# drums_01_1.net
KiCad netlist of a schematic drawn in EAGLE
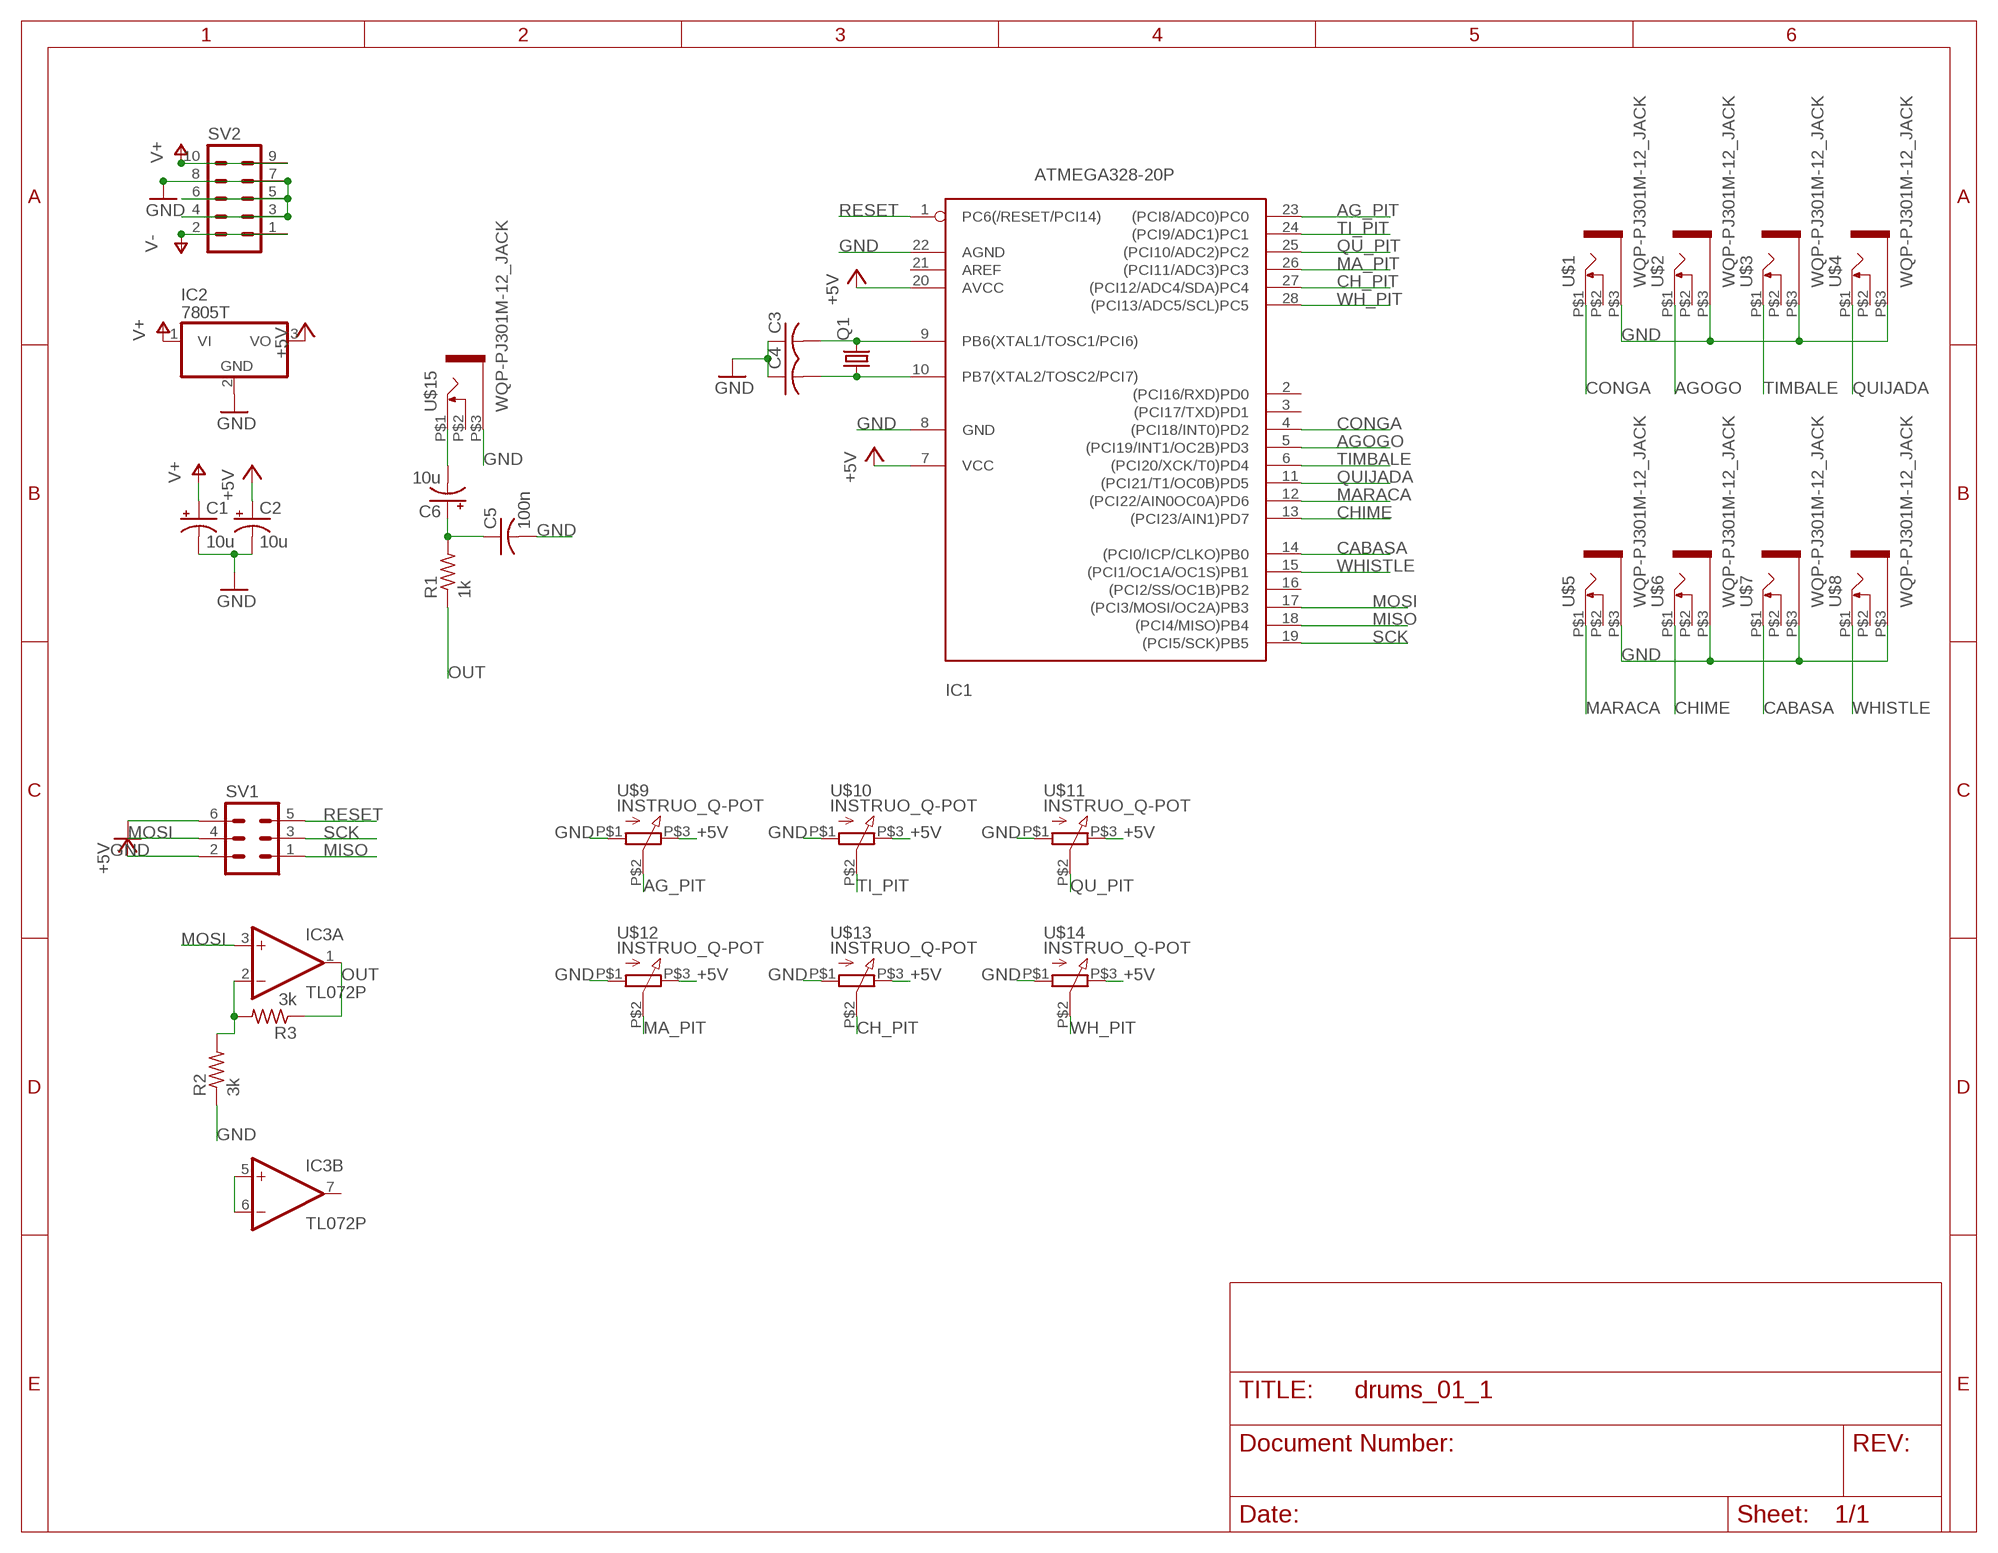
[diagram p0: schematic, sheet 1]

(export (version "E")
  (design (tool "Eeschema 10.0.6"))
  (components
    (comp (ref "C1")
      (value "10u")
      (footprint "eagle-import:E2,5-6")
      (libsource (lib "eagle-import") (part "CPOL-USE2.5-6"))
    )
    (comp (ref "C2")
      (value "10u")
      (footprint "eagle-import:E2,5-6")
      (libsource (lib "eagle-import") (part "CPOL-USE2.5-6"))
    )
    (comp (ref "C3")
      (value "C-US025-024X044")
      (footprint "eagle-import:C025-024X044")
      (libsource (lib "eagle-import") (part "C-US025-024X044"))
    )
    (comp (ref "C4")
      (value "C-US025-024X044")
      (footprint "eagle-import:C025-024X044")
      (libsource (lib "eagle-import") (part "C-US025-024X044"))
    )
    (comp (ref "C5")
      (value "100n")
      (footprint "eagle-import:C025-024X044")
      (libsource (lib "eagle-import") (part "C-US025-024X044"))
    )
    (comp (ref "C6")
      (value "10u")
      (footprint "eagle-import:E2,5-6")
      (libsource (lib "eagle-import") (part "CPOL-USE2.5-6"))
    )
    (comp (ref "IC1")
      (value "ATMEGA328-20P")
      (footprint "eagle-import:DIL28-3")
      (libsource (lib "eagle-import") (part "ATMEGA328P-20"))
    )
    (comp (ref "IC2")
      (value "7805T")
      (footprint "eagle-import:TO220H")
      (libsource (lib "eagle-import") (part "78T05"))
    )
    (comp (ref "IC3")
      (value "TL072P")
      (footprint "eagle-import:DIL08")
      (libsource (lib "eagle-import") (part "TL072P"))
    )
    (comp (ref "Q1")
      (value "CRYSTALHC49U-V")
      (footprint "eagle-import:HC49U-V")
      (libsource (lib "eagle-import") (part "CRYSTALHC49U-V"))
    )
    (comp (ref "R1")
      (value "1k")
      (footprint "eagle-import:0207_12")
      (libsource (lib "eagle-import") (part "R-US_0207/12"))
    )
    (comp (ref "R2")
      (value "3k")
      (footprint "eagle-import:0207_12")
      (libsource (lib "eagle-import") (part "R-US_0207/12"))
    )
    (comp (ref "R3")
      (value "3k")
      (footprint "eagle-import:0207_12")
      (libsource (lib "eagle-import") (part "R-US_0207/12"))
    )
    (comp (ref "SV1")
      (value "MA03-2")
      (footprint "eagle-import:MA03-2")
      (libsource (lib "eagle-import") (part "MA03-2"))
    )
    (comp (ref "SV2")
      (value "MA05-2")
      (footprint "eagle-import:MA05-2")
      (libsource (lib "eagle-import") (part "MA05-2"))
    )
    (comp (ref "U$1")
      (value "WQP-PJ301M-12_JACK")
      (footprint "eagle-import:WQP-PJ301M-12_JACK")
      (libsource (lib "eagle-import") (part "WQP-PJ301M-12_JACK"))
    )
    (comp (ref "U$2")
      (value "WQP-PJ301M-12_JACK")
      (footprint "eagle-import:WQP-PJ301M-12_JACK")
      (libsource (lib "eagle-import") (part "WQP-PJ301M-12_JACK"))
    )
    (comp (ref "U$3")
      (value "WQP-PJ301M-12_JACK")
      (footprint "eagle-import:WQP-PJ301M-12_JACK")
      (libsource (lib "eagle-import") (part "WQP-PJ301M-12_JACK"))
    )
    (comp (ref "U$4")
      (value "WQP-PJ301M-12_JACK")
      (footprint "eagle-import:WQP-PJ301M-12_JACK")
      (libsource (lib "eagle-import") (part "WQP-PJ301M-12_JACK"))
    )
    (comp (ref "U$5")
      (value "WQP-PJ301M-12_JACK")
      (footprint "eagle-import:WQP-PJ301M-12_JACK")
      (libsource (lib "eagle-import") (part "WQP-PJ301M-12_JACK"))
    )
    (comp (ref "U$6")
      (value "WQP-PJ301M-12_JACK")
      (footprint "eagle-import:WQP-PJ301M-12_JACK")
      (libsource (lib "eagle-import") (part "WQP-PJ301M-12_JACK"))
    )
    (comp (ref "U$7")
      (value "WQP-PJ301M-12_JACK")
      (footprint "eagle-import:WQP-PJ301M-12_JACK")
      (libsource (lib "eagle-import") (part "WQP-PJ301M-12_JACK"))
    )
    (comp (ref "U$8")
      (value "WQP-PJ301M-12_JACK")
      (footprint "eagle-import:WQP-PJ301M-12_JACK")
      (libsource (lib "eagle-import") (part "WQP-PJ301M-12_JACK"))
    )
    (comp (ref "U$9")
      (value "INSTRUO_Q-POT")
      (footprint "eagle-import:INSTRUO_Q-POT")
      (libsource (lib "eagle-import") (part "INSTRUO_Q-POT"))
    )
    (comp (ref "U$10")
      (value "INSTRUO_Q-POT")
      (footprint "eagle-import:INSTRUO_Q-POT")
      (libsource (lib "eagle-import") (part "INSTRUO_Q-POT"))
    )
    (comp (ref "U$11")
      (value "INSTRUO_Q-POT")
      (footprint "eagle-import:INSTRUO_Q-POT")
      (libsource (lib "eagle-import") (part "INSTRUO_Q-POT"))
    )
    (comp (ref "U$12")
      (value "INSTRUO_Q-POT")
      (footprint "eagle-import:INSTRUO_Q-POT")
      (libsource (lib "eagle-import") (part "INSTRUO_Q-POT"))
    )
    (comp (ref "U$13")
      (value "INSTRUO_Q-POT")
      (footprint "eagle-import:INSTRUO_Q-POT")
      (libsource (lib "eagle-import") (part "INSTRUO_Q-POT"))
    )
    (comp (ref "U$14")
      (value "INSTRUO_Q-POT")
      (footprint "eagle-import:INSTRUO_Q-POT")
      (libsource (lib "eagle-import") (part "INSTRUO_Q-POT"))
    )
    (comp (ref "U$15")
      (value "WQP-PJ301M-12_JACK")
      (footprint "eagle-import:WQP-PJ301M-12_JACK")
      (libsource (lib "eagle-import") (part "WQP-PJ301M-12_JACK"))
    )
  )
  (nets
    (net (code "1") (name "+5V") (class "Default")
      (node (ref "C2") (pin "+") (pinfunction "+_+") (pintype "passive"))
      (node (ref "IC1") (pin "20") (pinfunction "AVCC_20") (pintype "bidirectional"))
      (node (ref "IC1") (pin "7") (pinfunction "VCC_7") (pintype "bidirectional"))
      (node (ref "IC2") (pin "3") (pinfunction "VO_3") (pintype "passive"))
      (node (ref "SV1") (pin "2") (pinfunction "2_2") (pintype "passive"))
      (node (ref "U$10") (pin "P$3") (pinfunction "3_P$3") (pintype "passive"))
      (node (ref "U$11") (pin "P$3") (pinfunction "3_P$3") (pintype "passive"))
      (node (ref "U$12") (pin "P$3") (pinfunction "3_P$3") (pintype "passive"))
      (node (ref "U$13") (pin "P$3") (pinfunction "3_P$3") (pintype "passive"))
      (node (ref "U$14") (pin "P$3") (pinfunction "3_P$3") (pintype "passive"))
      (node (ref "U$9") (pin "P$3") (pinfunction "3_P$3") (pintype "passive"))
    )
    (net (code "2") (name "/AGOGO") (class "Default")
      (node (ref "IC1") (pin "5") (pinfunction "(PCI19/INT1/OC2B)PD3_5") (pintype "bidirectional"))
      (node (ref "U$2") (pin "P$1") (pinfunction "2_P$1") (pintype "passive"))
    )
    (net (code "3") (name "/AG_PIT") (class "Default")
      (node (ref "IC1") (pin "23") (pinfunction "(PCI8/ADC0)PC0_23") (pintype "bidirectional"))
      (node (ref "U$9") (pin "P$2") (pinfunction "2_P$2") (pintype "passive"))
    )
    (net (code "4") (name "/CABASA") (class "Default")
      (node (ref "IC1") (pin "14") (pinfunction "(PCI0/ICP/CLKO)PB0_14") (pintype "bidirectional"))
      (node (ref "U$7") (pin "P$1") (pinfunction "2_P$1") (pintype "passive"))
    )
    (net (code "5") (name "/CHIME") (class "Default")
      (node (ref "IC1") (pin "13") (pinfunction "(PCI23/AIN1)PD7_13") (pintype "bidirectional"))
      (node (ref "U$6") (pin "P$1") (pinfunction "2_P$1") (pintype "passive"))
    )
    (net (code "6") (name "/CH_PIT") (class "Default")
      (node (ref "IC1") (pin "27") (pinfunction "(PCI12/ADC4/SDA)PC4_27") (pintype "bidirectional"))
      (node (ref "U$13") (pin "P$2") (pinfunction "2_P$2") (pintype "passive"))
    )
    (net (code "7") (name "/CONGA") (class "Default")
      (node (ref "IC1") (pin "4") (pinfunction "(PCI18/INT0)PD2_4") (pintype "bidirectional"))
      (node (ref "U$1") (pin "P$1") (pinfunction "2_P$1") (pintype "passive"))
    )
    (net (code "8") (name "/MARACA") (class "Default")
      (node (ref "IC1") (pin "12") (pinfunction "(PCI22/AIN0OC0A)PD6_12") (pintype "bidirectional"))
      (node (ref "U$5") (pin "P$1") (pinfunction "2_P$1") (pintype "passive"))
    )
    (net (code "9") (name "/MA_PIT") (class "Default")
      (node (ref "IC1") (pin "26") (pinfunction "(PCI11/ADC3)PC3_26") (pintype "bidirectional"))
      (node (ref "U$12") (pin "P$2") (pinfunction "2_P$2") (pintype "passive"))
    )
    (net (code "10") (name "/MISO") (class "Default")
      (node (ref "IC1") (pin "18") (pinfunction "(PCI4/MISO)PB4_18") (pintype "bidirectional"))
      (node (ref "SV1") (pin "1") (pinfunction "1_1") (pintype "passive"))
    )
    (net (code "11") (name "/MOSI") (class "Default")
      (node (ref "IC1") (pin "17") (pinfunction "(PCI3/MOSI/OC2A)PB3_17") (pintype "bidirectional"))
      (node (ref "IC3") (pin "3") (pinfunction "+IN_3") (pintype "input"))
      (node (ref "SV1") (pin "4") (pinfunction "4_4") (pintype "passive"))
    )
    (net (code "12") (name "/OUT") (class "Default")
      (node (ref "IC3") (pin "1") (pinfunction "OUT_1") (pintype "output"))
      (node (ref "R1") (pin "1") (pinfunction "1_1") (pintype "passive"))
      (node (ref "R3") (pin "1") (pinfunction "1_1") (pintype "passive"))
    )
    (net (code "13") (name "/QUIJADA") (class "Default")
      (node (ref "IC1") (pin "11") (pinfunction "(PCI21/T1/OC0B)PD5_11") (pintype "bidirectional"))
      (node (ref "U$4") (pin "P$1") (pinfunction "2_P$1") (pintype "passive"))
    )
    (net (code "14") (name "/QU_PIT") (class "Default")
      (node (ref "IC1") (pin "25") (pinfunction "(PCI10/ADC2)PC2_25") (pintype "bidirectional"))
      (node (ref "U$11") (pin "P$2") (pinfunction "2_P$2") (pintype "passive"))
    )
    (net (code "15") (name "/RESET") (class "Default")
      (node (ref "IC1") (pin "1") (pinfunction "PC6(/RESET/PCI14)_1") (pintype "bidirectional"))
      (node (ref "SV1") (pin "5") (pinfunction "5_5") (pintype "passive"))
    )
    (net (code "16") (name "/SCK") (class "Default")
      (node (ref "IC1") (pin "19") (pinfunction "(PCI5/SCK)PB5_19") (pintype "bidirectional"))
      (node (ref "SV1") (pin "3") (pinfunction "3_3") (pintype "passive"))
    )
    (net (code "17") (name "/TIMBALE") (class "Default")
      (node (ref "IC1") (pin "6") (pinfunction "(PCI20/XCK/T0)PD4_6") (pintype "bidirectional"))
      (node (ref "U$3") (pin "P$1") (pinfunction "2_P$1") (pintype "passive"))
    )
    (net (code "18") (name "/TI_PIT") (class "Default")
      (node (ref "IC1") (pin "24") (pinfunction "(PCI9/ADC1)PC1_24") (pintype "bidirectional"))
      (node (ref "U$10") (pin "P$2") (pinfunction "2_P$2") (pintype "passive"))
    )
    (net (code "19") (name "/WHISTLE") (class "Default")
      (node (ref "IC1") (pin "15") (pinfunction "(PCI1/OC1A/OC1S)PB1_15") (pintype "bidirectional"))
      (node (ref "U$8") (pin "P$1") (pinfunction "2_P$1") (pintype "passive"))
    )
    (net (code "20") (name "/WH_PIT") (class "Default")
      (node (ref "IC1") (pin "28") (pinfunction "(PCI13/ADC5/SCL)PC5_28") (pintype "bidirectional"))
      (node (ref "U$14") (pin "P$2") (pinfunction "2_P$2") (pintype "passive"))
    )
    (net (code "21") (name "GND") (class "Default")
      (node (ref "C1") (pin "-") (pinfunction "-_-") (pintype "passive"))
      (node (ref "C2") (pin "-") (pinfunction "-_-") (pintype "passive"))
      (node (ref "C3") (pin "1") (pinfunction "1_1") (pintype "passive"))
      (node (ref "C4") (pin "1") (pinfunction "1_1") (pintype "passive"))
      (node (ref "C5") (pin "2") (pinfunction "2_2") (pintype "passive"))
      (node (ref "IC1") (pin "22") (pinfunction "AGND_22") (pintype "bidirectional"))
      (node (ref "IC1") (pin "8") (pinfunction "GND_8") (pintype "bidirectional"))
      (node (ref "IC2") (pin "2") (pinfunction "GND_2") (pintype "passive"))
      (node (ref "R2") (pin "1") (pinfunction "1_1") (pintype "passive"))
      (node (ref "SV1") (pin "6") (pinfunction "6_6") (pintype "passive"))
      (node (ref "SV2") (pin "3") (pinfunction "3_3") (pintype "passive"))
      (node (ref "SV2") (pin "4") (pinfunction "4_4") (pintype "passive"))
      (node (ref "SV2") (pin "5") (pinfunction "5_5") (pintype "passive"))
      (node (ref "SV2") (pin "6") (pinfunction "6_6") (pintype "passive"))
      (node (ref "SV2") (pin "7") (pinfunction "7_7") (pintype "passive"))
      (node (ref "SV2") (pin "8") (pinfunction "8_8") (pintype "passive"))
      (node (ref "U$1") (pin "P$3") (pinfunction "1_P$3") (pintype "passive"))
      (node (ref "U$10") (pin "P$1") (pinfunction "1_P$1") (pintype "passive"))
      (node (ref "U$11") (pin "P$1") (pinfunction "1_P$1") (pintype "passive"))
      (node (ref "U$12") (pin "P$1") (pinfunction "1_P$1") (pintype "passive"))
      (node (ref "U$13") (pin "P$1") (pinfunction "1_P$1") (pintype "passive"))
      (node (ref "U$14") (pin "P$1") (pinfunction "1_P$1") (pintype "passive"))
      (node (ref "U$15") (pin "P$3") (pinfunction "1_P$3") (pintype "passive"))
      (node (ref "U$2") (pin "P$3") (pinfunction "1_P$3") (pintype "passive"))
      (node (ref "U$3") (pin "P$3") (pinfunction "1_P$3") (pintype "passive"))
      (node (ref "U$4") (pin "P$3") (pinfunction "1_P$3") (pintype "passive"))
      (node (ref "U$5") (pin "P$3") (pinfunction "1_P$3") (pintype "passive"))
      (node (ref "U$6") (pin "P$3") (pinfunction "1_P$3") (pintype "passive"))
      (node (ref "U$7") (pin "P$3") (pinfunction "1_P$3") (pintype "passive"))
      (node (ref "U$8") (pin "P$3") (pinfunction "1_P$3") (pintype "passive"))
      (node (ref "U$9") (pin "P$1") (pinfunction "1_P$1") (pintype "passive"))
    )
    (net (code "22") (name "Net-(C5-Pad1)") (class "Default")
      (node (ref "C5") (pin "1") (pinfunction "1_1") (pintype "passive"))
      (node (ref "C6") (pin "+") (pinfunction "+_+") (pintype "passive"))
      (node (ref "R1") (pin "2") (pinfunction "2_2") (pintype "passive"))
    )
    (net (code "23") (name "Net-(IC1-PB6(XTAL1{slash}TOSC1{slash}PCI6))") (class "Default")
      (node (ref "C3") (pin "2") (pinfunction "2_2") (pintype "passive"))
      (node (ref "IC1") (pin "9") (pinfunction "PB6(XTAL1/TOSC1/PCI6)_9") (pintype "bidirectional"))
      (node (ref "Q1") (pin "2") (pinfunction "2_2") (pintype "passive"))
    )
    (net (code "24") (name "Net-(IC1-PB7(XTAL2{slash}TOSC2{slash}PCI7))") (class "Default")
      (node (ref "C4") (pin "2") (pinfunction "2_2") (pintype "passive"))
      (node (ref "IC1") (pin "10") (pinfunction "PB7(XTAL2/TOSC2/PCI7)_10") (pintype "bidirectional"))
      (node (ref "Q1") (pin "1") (pinfunction "1_1") (pintype "passive"))
    )
    (net (code "25") (name "Net-(IC3A--IN)") (class "Default")
      (node (ref "IC3") (pin "2") (pinfunction "-IN_2") (pintype "input"))
      (node (ref "R2") (pin "2") (pinfunction "2_2") (pintype "passive"))
      (node (ref "R3") (pin "2") (pinfunction "2_2") (pintype "passive"))
    )
    (net (code "26") (name "Net-(IC3B-+IN)") (class "Default")
      (node (ref "IC3") (pin "5") (pinfunction "+IN_5") (pintype "input"))
      (node (ref "IC3") (pin "6") (pinfunction "-IN_6") (pintype "input"))
    )
    (net (code "27") (name "Net-(U$15-2)") (class "Default")
      (node (ref "C6") (pin "-") (pinfunction "-_-") (pintype "passive"))
      (node (ref "U$15") (pin "P$1") (pinfunction "2_P$1") (pintype "passive"))
    )
    (net (code "28") (name "V+") (class "Default")
      (node (ref "C1") (pin "+") (pinfunction "+_+") (pintype "passive"))
      (node (ref "IC2") (pin "1") (pinfunction "VI_1") (pintype "input"))
      (node (ref "SV2") (pin "10") (pinfunction "10_10") (pintype "passive"))
      (node (ref "SV2") (pin "9") (pinfunction "9_9") (pintype "passive"))
    )
    (net (code "29") (name "V-") (class "Default")
      (node (ref "SV2") (pin "1") (pinfunction "1_1") (pintype "passive"))
      (node (ref "SV2") (pin "2") (pinfunction "2_2") (pintype "passive"))
    )
    (net (code "30") (name "unconnected-(IC1-(PCI2{slash}SS{slash}OC1B)PB2-Pad16)") (class "Default")
      (node (ref "IC1") (pin "16") (pinfunction "(PCI2/SS/OC1B)PB2_16") (pintype "bidirectional"))
    )
    (net (code "31") (name "unconnected-(IC1-(PCI16{slash}RXD)PD0-Pad2)") (class "Default")
      (node (ref "IC1") (pin "2") (pinfunction "(PCI16/RXD)PD0_2") (pintype "bidirectional"))
    )
    (net (code "32") (name "unconnected-(IC1-(PCI17{slash}TXD)PD1-Pad3)") (class "Default")
      (node (ref "IC1") (pin "3") (pinfunction "(PCI17/TXD)PD1_3") (pintype "bidirectional"))
    )
    (net (code "33") (name "unconnected-(IC1-AREF-Pad21)") (class "Default")
      (node (ref "IC1") (pin "21") (pinfunction "AREF_21") (pintype "bidirectional"))
    )
    (net (code "34") (name "unconnected-(IC3B-OUT-Pad7)") (class "Default")
      (node (ref "IC3") (pin "7") (pinfunction "OUT_7") (pintype "output"))
    )
    (net (code "35") (name "unconnected-(U$1-3-PadP$2)") (class "Default")
      (node (ref "U$1") (pin "P$2") (pinfunction "3_P$2") (pintype "passive"))
    )
    (net (code "36") (name "unconnected-(U$2-3-PadP$2)") (class "Default")
      (node (ref "U$2") (pin "P$2") (pinfunction "3_P$2") (pintype "passive"))
    )
    (net (code "37") (name "unconnected-(U$3-3-PadP$2)") (class "Default")
      (node (ref "U$3") (pin "P$2") (pinfunction "3_P$2") (pintype "passive"))
    )
    (net (code "38") (name "unconnected-(U$4-3-PadP$2)") (class "Default")
      (node (ref "U$4") (pin "P$2") (pinfunction "3_P$2") (pintype "passive"))
    )
    (net (code "39") (name "unconnected-(U$5-3-PadP$2)") (class "Default")
      (node (ref "U$5") (pin "P$2") (pinfunction "3_P$2") (pintype "passive"))
    )
    (net (code "40") (name "unconnected-(U$6-3-PadP$2)") (class "Default")
      (node (ref "U$6") (pin "P$2") (pinfunction "3_P$2") (pintype "passive"))
    )
    (net (code "41") (name "unconnected-(U$7-3-PadP$2)") (class "Default")
      (node (ref "U$7") (pin "P$2") (pinfunction "3_P$2") (pintype "passive"))
    )
    (net (code "42") (name "unconnected-(U$8-3-PadP$2)") (class "Default")
      (node (ref "U$8") (pin "P$2") (pinfunction "3_P$2") (pintype "passive"))
    )
    (net (code "43") (name "unconnected-(U$15-3-PadP$2)") (class "Default")
      (node (ref "U$15") (pin "P$2") (pinfunction "3_P$2") (pintype "passive"))
    )
  )
)
